# XM-15B_Typical_Application_Circuit.net
KiCad netlist of a schematic drawn in Altium Designer
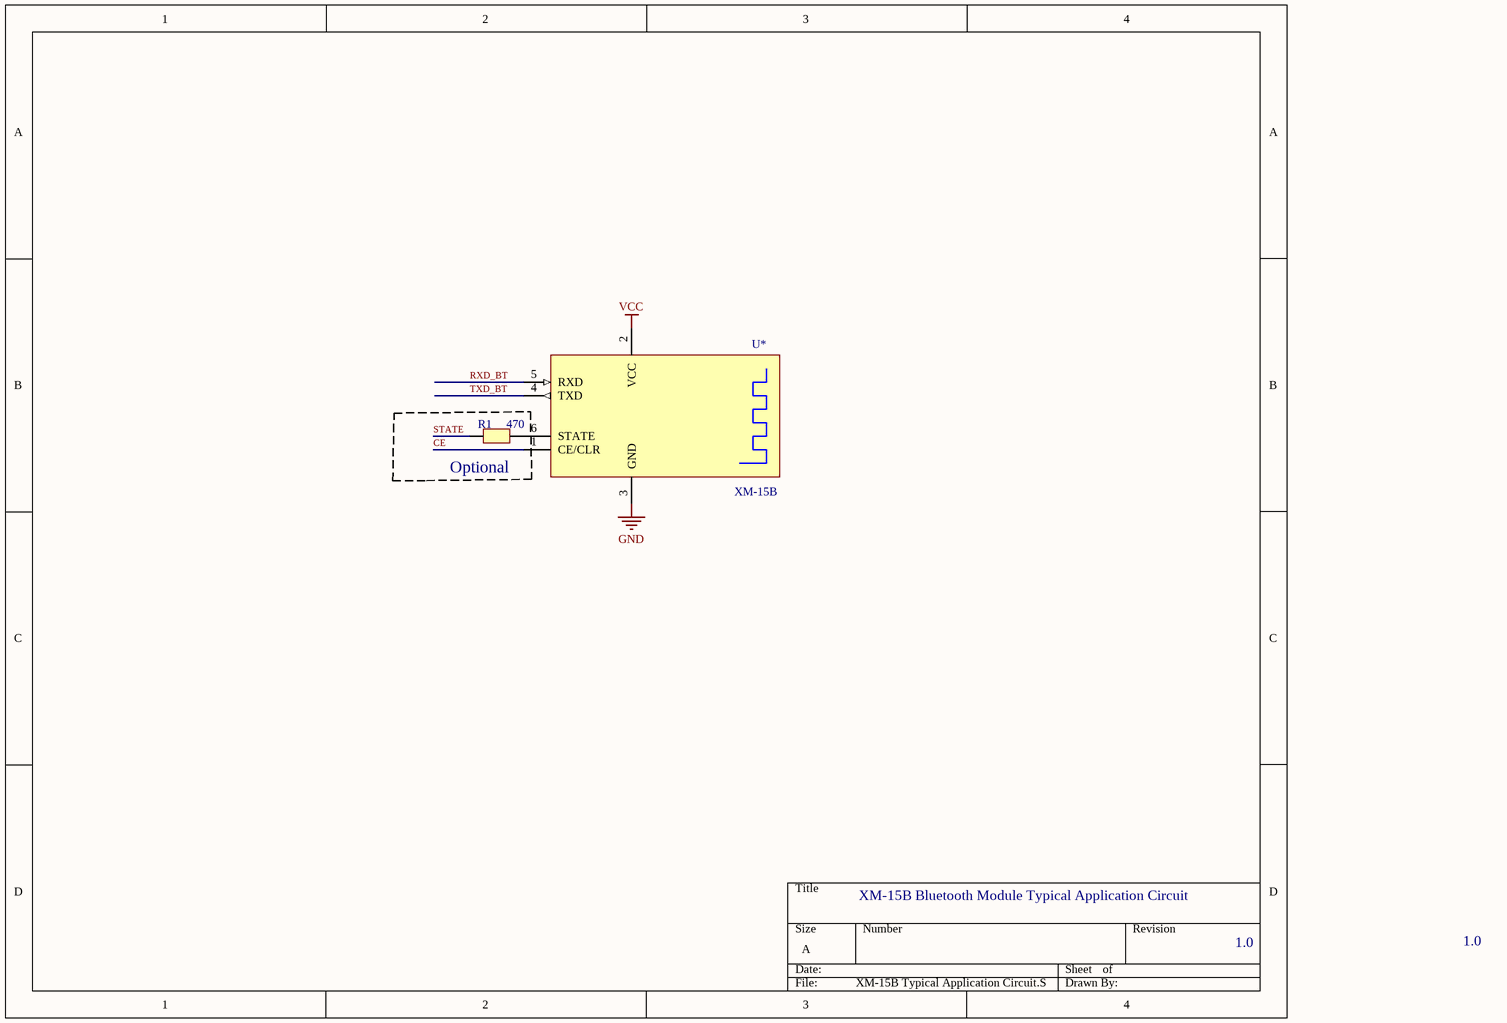
[diagram p0: XM-15B Typical Application Circuit.SchDoc]

(export (version "E")
  (design (tool "Eeschema 10.0.6"))
  (components
    (comp (ref "R1") (value "470") (footprint "0603.RC") (libsource (lib "wbh") (part "RES")))
    (comp (ref "U*") (value "XM-15B") (footprint "XM-05") (libsource (lib "XM-15B") (part "XM-15B")))
  )
  (nets
    (net (code "1") (name "/CE") (class "Default")
      (node (ref "U*") (pin "1") (pinfunction "CE/CLR_1") (pintype "passive"))
    )
    (net (code "2") (name "/RXD_BT") (class "Default")
      (node (ref "U*") (pin "5") (pinfunction "RXD_5") (pintype "input"))
    )
    (net (code "3") (name "/STATE") (class "Default")
      (node (ref "R1") (pin "2") (pinfunction "2_2") (pintype "passive"))
    )
    (net (code "4") (name "/TXD_BT") (class "Default")
      (node (ref "U*") (pin "4") (pinfunction "TXD_4") (pintype "output"))
    )
    (net (code "5") (name "GND") (class "Default")
      (node (ref "U*") (pin "3") (pinfunction "GND_3") (pintype "passive"))
    )
    (net (code "6") (name "Net-(U*-STATE)") (class "Default")
      (node (ref "R1") (pin "1") (pinfunction "1_1") (pintype "passive"))
      (node (ref "U*") (pin "6") (pinfunction "STATE_6") (pintype "passive"))
    )
    (net (code "7") (name "VCC") (class "Default")
      (node (ref "U*") (pin "2") (pinfunction "VCC_2") (pintype "power_in"))
    )
  )
)
